# Mikrobus_v2.net
KiCad netlist of a schematic drawn in Altium Designer
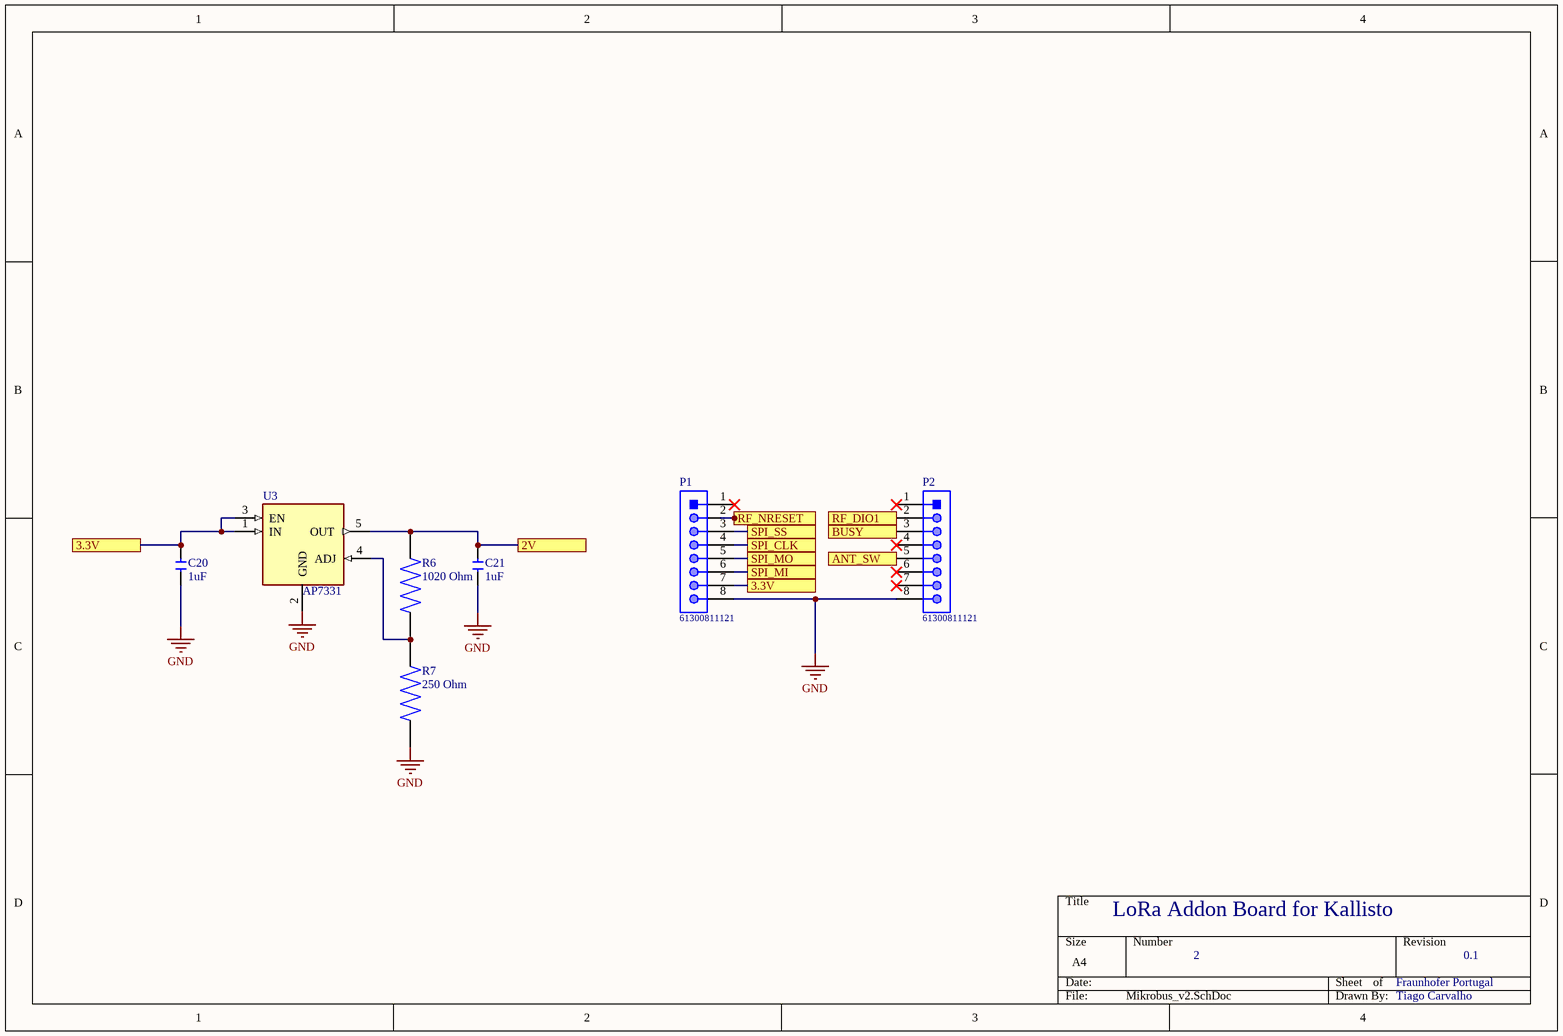
[diagram p0: Mikrobus_v2.SchDoc]

(export (version "E")
  (design (tool "Eeschema 10.0.6"))
  (components
    (comp (ref "C20")
      (value "1uF")
      (footprint "C0402")
      (description "1ÂµF Â±10% 10V Ceramic Capacitor X5R 0402 _1005 Metric_")
      (fields (field (name "MP") "CC0402KRX5R6BB105") (field (name "MF") "Yageo"))
      (libsource (lib "C_1uF") (part "CERAMIC-1UF-10V-10%-X5R(0402)"))
    )
    (comp (ref "C21")
      (value "1uF")
      (footprint "C0402")
      (description "1ÂµF Â±10% 10V Ceramic Capacitor X5R 0402 _1005 Metric_")
      (fields (field (name "MP") "CC0402KRX5R6BB105") (field (name "MF") "Yageo"))
      (libsource (lib "C_1uF") (part "CERAMIC-1UF-10V-10%-X5R(0402)"))
    )
    (comp (ref "P1")
      (value "61300811121")
      (footprint "61300811121")
      (description "THT Vertical Pin Header WR-PHD, Pitch 2.54 mm, Single Row, 8 pins")
      (fields (field (name "MANUFACTURER") "Wurth Elektronik") (field (name "PUBLISHER") "WurthElektronik"))
      (libsource (lib "Altium Content Vault") (part "WE-CN-1P-M-R8"))
    )
    (comp (ref "P2")
      (value "61300811121")
      (footprint "61300811121")
      (description "THT Vertical Pin Header WR-PHD, Pitch 2.54 mm, Single Row, 8 pins")
      (fields (field (name "MANUFACTURER") "Wurth Elektronik") (field (name "PUBLISHER") "WurthElektronik"))
      (libsource (lib "") (part "WE-CN-1P-M-R8_1"))
    )
    (comp (ref "R6")
      (value "1020 Ohm")
      (footprint "RESC1005X40N")
      (description "Res Thick Film 0402 1.02K Ohm 1% 1/16W Â±100ppm/Â°C Molded SMD SMD Paper T/R")
      (fields (field (name "MP") "CRCW04021K02FKTD"))
      (libsource (lib "R_1K02") (part "CRCW04021K02FKTD"))
    )
    (comp (ref "R7")
      (value "250 Ohm")
      (footprint "RESC1005X35N")
      (fields (field (name "MP") "CRCW0402255RFKEDC"))
      (libsource (lib "R_255") (part "CRCW0402255RFKEDC"))
    )
    (comp (ref "U3")
      (value "AP7331")
      (footprint "SOT95P285X145-5N")
      (description "Linear Voltage Regulator IC 1 Output 300mA SOT-25")
      (fields (field (name "MP") "AP7331-18WG-7") (field (name "MF") "Diodes Inc."))
      (libsource (lib "conversor") (part "AP7331-18WG-7"))
    )
  )
  (nets
    (net (code "1") (name "/2V") (class "Default")
      (node (ref "C21") (pin "2") (pinfunction "2_2") (pintype "passive"))
      (node (ref "R6") (pin "2") (pinfunction "2_2") (pintype "passive"))
      (node (ref "U3") (pin "5") (pinfunction "OUT_5") (pintype "output"))
    )
    (net (code "2") (name "/3.3V") (class "Default")
      (node (ref "C20") (pin "2") (pinfunction "2_2") (pintype "passive"))
      (node (ref "P1") (pin "7") (pinfunction "7_7") (pintype "passive"))
      (node (ref "U3") (pin "1") (pinfunction "IN_1") (pintype "input"))
      (node (ref "U3") (pin "3") (pinfunction "EN_3") (pintype "input"))
    )
    (net (code "3") (name "/ANT_SW") (class "Default")
      (node (ref "P2") (pin "5") (pinfunction "5_5") (pintype "passive"))
    )
    (net (code "4") (name "/BUSY") (class "Default")
      (node (ref "P2") (pin "3") (pinfunction "3_3") (pintype "passive"))
    )
    (net (code "5") (name "/RF_DIO1") (class "Default")
      (node (ref "P2") (pin "2") (pinfunction "2_2") (pintype "passive"))
    )
    (net (code "6") (name "/RF_NRESET") (class "Default")
      (node (ref "P1") (pin "2") (pinfunction "2_2") (pintype "passive"))
    )
    (net (code "7") (name "/SPI_CLK") (class "Default")
      (node (ref "P1") (pin "4") (pinfunction "4_4") (pintype "passive"))
    )
    (net (code "8") (name "/SPI_MI") (class "Default")
      (node (ref "P1") (pin "6") (pinfunction "6_6") (pintype "passive"))
    )
    (net (code "9") (name "/SPI_MO") (class "Default")
      (node (ref "P1") (pin "5") (pinfunction "5_5") (pintype "passive"))
    )
    (net (code "10") (name "/SPI_SS") (class "Default")
      (node (ref "P1") (pin "3") (pinfunction "3_3") (pintype "passive"))
    )
    (net (code "11") (name "GND") (class "Default")
      (node (ref "C20") (pin "1") (pinfunction "1_1") (pintype "passive"))
      (node (ref "C21") (pin "1") (pinfunction "1_1") (pintype "passive"))
      (node (ref "P1") (pin "8") (pinfunction "8_8") (pintype "passive"))
      (node (ref "P2") (pin "8") (pinfunction "8_8") (pintype "passive"))
      (node (ref "R7") (pin "1") (pinfunction "1_1") (pintype "passive"))
      (node (ref "U3") (pin "2") (pinfunction "GND_2") (pintype "power_in"))
    )
    (net (code "12") (name "Net-(U3-ADJ)") (class "Default")
      (node (ref "R6") (pin "1") (pinfunction "1_1") (pintype "passive"))
      (node (ref "R7") (pin "2") (pinfunction "2_2") (pintype "passive"))
      (node (ref "U3") (pin "4") (pinfunction "ADJ_4") (pintype "input"))
    )
    (net (code "13") (name "unconnected-(P1-Pad1)") (class "Default")
      (node (ref "P1") (pin "1") (pinfunction "1_1") (pintype "passive+no_connect"))
    )
    (net (code "14") (name "unconnected-(P2-Pad1)") (class "Default")
      (node (ref "P2") (pin "1") (pinfunction "1_1") (pintype "passive+no_connect"))
    )
    (net (code "15") (name "unconnected-(P2-Pad4)") (class "Default")
      (node (ref "P2") (pin "4") (pinfunction "4_4") (pintype "passive+no_connect"))
    )
    (net (code "16") (name "unconnected-(P2-Pad6)") (class "Default")
      (node (ref "P2") (pin "6") (pinfunction "6_6") (pintype "passive+no_connect"))
    )
    (net (code "17") (name "unconnected-(P2-Pad7)") (class "Default")
      (node (ref "P2") (pin "7") (pinfunction "7_7") (pintype "passive+no_connect"))
    )
  )
)
